# PIC32MZ.net
KiCad netlist of a schematic drawn in Altium Designer
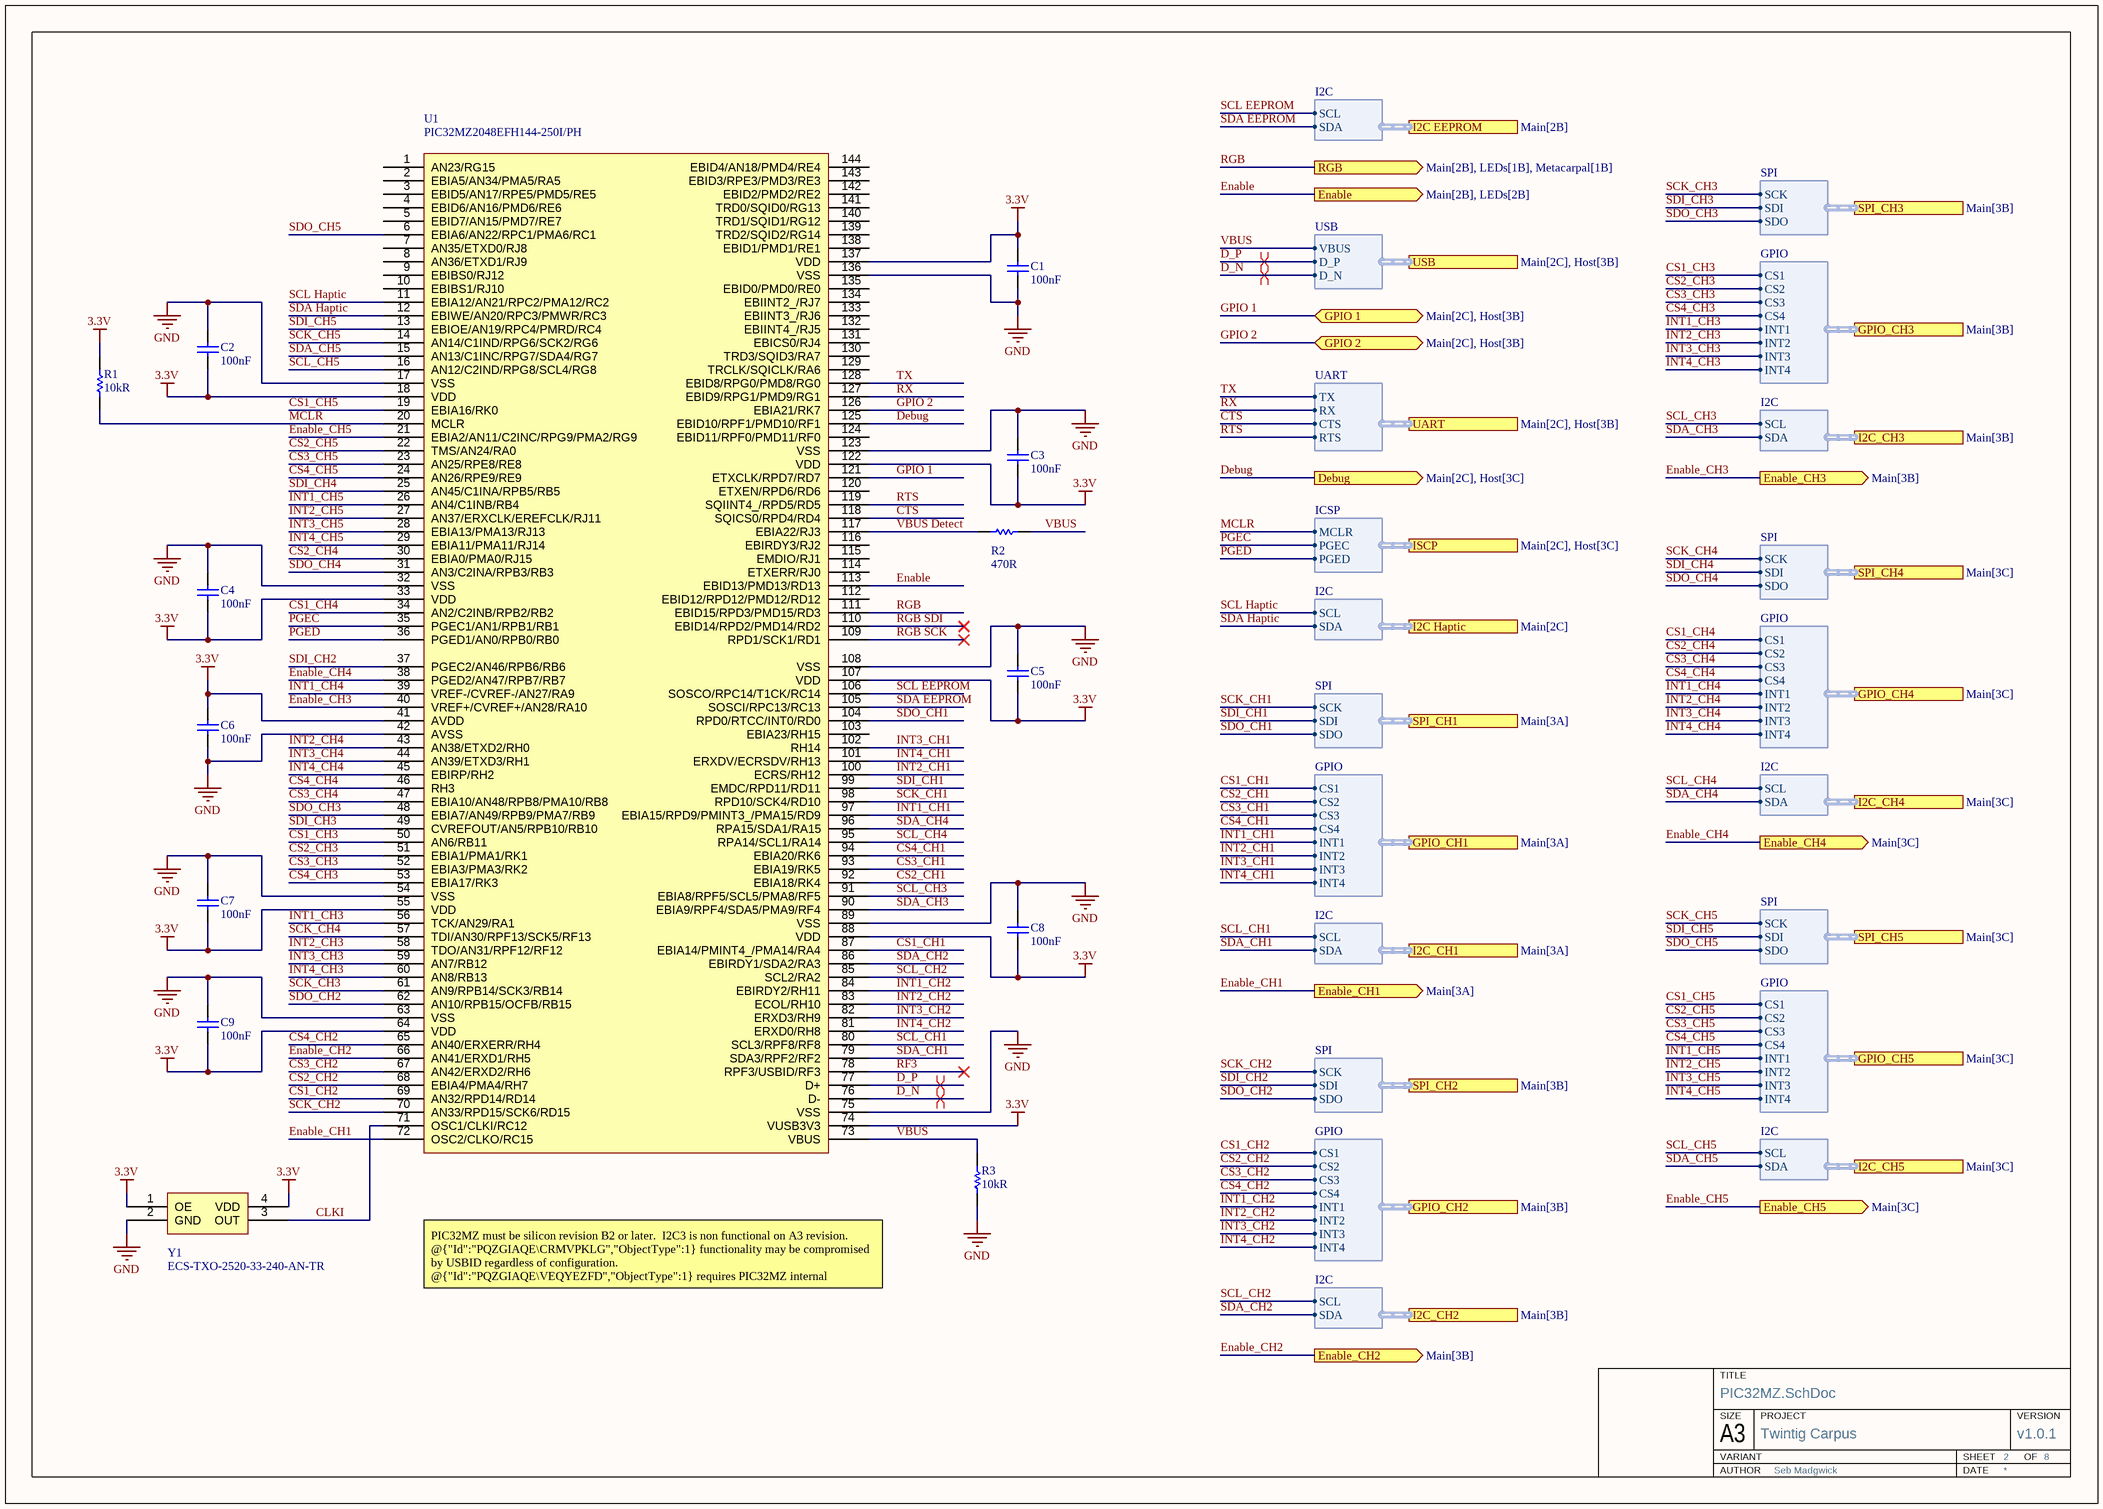
[diagram p0: PIC32MZ.SchDoc]

(export (version "E")
  (design (tool "Eeschema 10.0.6"))
  (components
    (comp (ref "C1") (value "100nF") (footprint "Capacitor 0402") (libsource (lib "x-io") (part "Capacitor")))
    (comp (ref "C2") (value "100nF") (footprint "Capacitor 0402") (libsource (lib "x-io") (part "Capacitor")))
    (comp (ref "C3") (value "100nF") (footprint "Capacitor 0402") (libsource (lib "x-io") (part "Capacitor")))
    (comp (ref "C4") (value "100nF") (footprint "Capacitor 0402") (libsource (lib "x-io") (part "Capacitor")))
    (comp (ref "C5") (value "100nF") (footprint "Capacitor 0402") (libsource (lib "x-io") (part "Capacitor")))
    (comp (ref "C6") (value "100nF") (footprint "Capacitor 0402") (libsource (lib "x-io") (part "Capacitor")))
    (comp (ref "C7") (value "100nF") (footprint "Capacitor 0402") (libsource (lib "x-io") (part "Capacitor")))
    (comp (ref "C8") (value "100nF") (footprint "Capacitor 0402") (libsource (lib "x-io") (part "Capacitor")))
    (comp (ref "C9") (value "100nF") (footprint "Capacitor 0402") (libsource (lib "x-io") (part "Capacitor")))
    (comp (ref "R1") (value "10kR") (footprint "Resistor 0402") (libsource (lib "x-io") (part "Resistor")))
    (comp (ref "R2") (value "470R") (footprint "Resistor 0402") (libsource (lib "x-io") (part "Resistor")))
    (comp (ref "R3") (value "10kR") (footprint "Resistor 0402") (libsource (lib "x-io") (part "Resistor")))
    (comp (ref "U1")
      (value "PIC32MZ2048EFH144-250I/PH")
      (footprint "TQFP-144 0.4mm")
      (libsource (lib "x-io") (part "PIC32MZ2048EFH144-250I/PH"))
    )
    (comp (ref "Y1")
      (value "ECS-TXO-2520-33-240-AN-TR")
      (footprint "ECS 2x2.5mm")
      (libsource (lib "x-io") (part "Oscillator"))
    )
  )
  (nets
    (net (code "7") (name "/CLKI") (class "Default")
      (node (ref "U1") (pin "71") (pinfunction "OSC1/CLKI/RC12_71") (pintype "passive"))
      (node (ref "Y1") (pin "3") (pinfunction "OUT_3") (pintype "passive"))
    )
    (net (code "8") (name "/CS1_CH1") (class "Default")
      (node (ref "U1") (pin "87") (pinfunction "EBIA14/PMINT4_/PMA14/RA4_87") (pintype "passive"))
    )
    (net (code "9") (name "/CS1_CH2") (class "Default")
      (node (ref "U1") (pin "69") (pinfunction "AN32/RPD14/RD14_69") (pintype "passive"))
    )
    (net (code "10") (name "/CS1_CH3") (class "Default")
      (node (ref "U1") (pin "50") (pinfunction "AN6/RB11_50") (pintype "passive"))
    )
    (net (code "11") (name "/CS1_CH4") (class "Default")
      (node (ref "U1") (pin "34") (pinfunction "AN2/C2INB/RPB2/RB2_34") (pintype "passive"))
    )
    (net (code "12") (name "/CS1_CH5") (class "Default")
      (node (ref "U1") (pin "19") (pinfunction "EBIA16/RK0_19") (pintype "passive"))
    )
    (net (code "13") (name "/CS2_CH1") (class "Default")
      (node (ref "U1") (pin "92") (pinfunction "EBIA18/RK4_92") (pintype "passive"))
    )
    (net (code "14") (name "/CS2_CH2") (class "Default")
      (node (ref "U1") (pin "68") (pinfunction "EBIA4/PMA4/RH7_68") (pintype "passive"))
    )
    (net (code "15") (name "/CS2_CH3") (class "Default")
      (node (ref "U1") (pin "51") (pinfunction "EBIA1/PMA1/RK1_51") (pintype "passive"))
    )
    (net (code "16") (name "/CS2_CH4") (class "Default")
      (node (ref "U1") (pin "30") (pinfunction "EBIA0/PMA0/RJ15_30") (pintype "passive"))
    )
    (net (code "17") (name "/CS2_CH5") (class "Default")
      (node (ref "U1") (pin "22") (pinfunction "TMS/AN24/RA0_22") (pintype "passive"))
    )
    (net (code "18") (name "/CS3_CH1") (class "Default")
      (node (ref "U1") (pin "93") (pinfunction "EBIA19/RK5_93") (pintype "passive"))
    )
    (net (code "19") (name "/CS3_CH2") (class "Default")
      (node (ref "U1") (pin "67") (pinfunction "AN42/ERXD2/RH6_67") (pintype "passive"))
    )
    (net (code "20") (name "/CS3_CH3") (class "Default")
      (node (ref "U1") (pin "52") (pinfunction "EBIA3/PMA3/RK2_52") (pintype "passive"))
    )
    (net (code "21") (name "/CS3_CH4") (class "Default")
      (node (ref "U1") (pin "47") (pinfunction "EBIA10/AN48/RPB8/PMA10/RB8_47") (pintype "passive"))
    )
    (net (code "22") (name "/CS3_CH5") (class "Default")
      (node (ref "U1") (pin "23") (pinfunction "AN25/RPE8/RE8_23") (pintype "passive"))
    )
    (net (code "23") (name "/CS4_CH1") (class "Default")
      (node (ref "U1") (pin "94") (pinfunction "EBIA20/RK6_94") (pintype "passive"))
    )
    (net (code "24") (name "/CS4_CH2") (class "Default")
      (node (ref "U1") (pin "65") (pinfunction "AN40/ERXERR/RH4_65") (pintype "passive"))
    )
    (net (code "25") (name "/CS4_CH3") (class "Default")
      (node (ref "U1") (pin "53") (pinfunction "EBIA17/RK3_53") (pintype "passive"))
    )
    (net (code "26") (name "/CS4_CH4") (class "Default")
      (node (ref "U1") (pin "46") (pinfunction "RH3_46") (pintype "passive"))
    )
    (net (code "27") (name "/CS4_CH5") (class "Default")
      (node (ref "U1") (pin "24") (pinfunction "AN26/RPE9/RE9_24") (pintype "passive"))
    )
    (net (code "28") (name "/CTS") (class "Default")
      (node (ref "U1") (pin "118") (pinfunction "SQICS0/RPD4/RD4_118") (pintype "passive"))
    )
    (net (code "29") (name "/D_N") (class "Default")
      (node (ref "U1") (pin "76") (pinfunction "D-_76") (pintype "passive"))
    )
    (net (code "30") (name "/D_P") (class "Default")
      (node (ref "U1") (pin "77") (pinfunction "D+_77") (pintype "passive"))
    )
    (net (code "31") (name "/Debug") (class "Default")
      (node (ref "U1") (pin "125") (pinfunction "EBID10/RPF1/PMD10/RF1_125") (pintype "passive"))
    )
    (net (code "32") (name "/Enable") (class "Default")
      (node (ref "U1") (pin "113") (pinfunction "EBID13/PMD13/RD13_113") (pintype "passive"))
    )
    (net (code "33") (name "/Enable_CH1") (class "Default")
      (node (ref "U1") (pin "72") (pinfunction "OSC2/CLKO/RC15_72") (pintype "passive"))
    )
    (net (code "34") (name "/Enable_CH2") (class "Default")
      (node (ref "U1") (pin "66") (pinfunction "AN41/ERXD1/RH5_66") (pintype "passive"))
    )
    (net (code "35") (name "/Enable_CH3") (class "Default")
      (node (ref "U1") (pin "40") (pinfunction "VREF+/CVREF+/AN28/RA10_40") (pintype "passive"))
    )
    (net (code "36") (name "/Enable_CH4") (class "Default")
      (node (ref "U1") (pin "38") (pinfunction "PGED2/AN47/RPB7/RB7_38") (pintype "passive"))
    )
    (net (code "37") (name "/Enable_CH5") (class "Default")
      (node (ref "U1") (pin "21") (pinfunction "EBIA2/AN11/C2INC/RPG9/PMA2/RG9_21") (pintype "passive"))
    )
    (net (code "38") (name "/GPIO 1") (class "Default")
      (node (ref "U1") (pin "121") (pinfunction "ETXCLK/RPD7/RD7_121") (pintype "passive"))
    )
    (net (code "39") (name "/GPIO 2") (class "Default")
      (node (ref "U1") (pin "126") (pinfunction "EBIA21/RK7_126") (pintype "passive"))
    )
    (net (code "40") (name "/INT1_CH1") (class "Default")
      (node (ref "U1") (pin "97") (pinfunction "EBIA15/RPD9/PMINT3_/PMA15/RD9_97") (pintype "passive"))
    )
    (net (code "41") (name "/INT1_CH2") (class "Default")
      (node (ref "U1") (pin "84") (pinfunction "EBIRDY2/RH11_84") (pintype "passive"))
    )
    (net (code "42") (name "/INT1_CH3") (class "Default")
      (node (ref "U1") (pin "56") (pinfunction "TCK/AN29/RA1_56") (pintype "passive"))
    )
    (net (code "43") (name "/INT1_CH4") (class "Default")
      (node (ref "U1") (pin "39") (pinfunction "VREF-/CVREF-/AN27/RA9_39") (pintype "passive"))
    )
    (net (code "44") (name "/INT1_CH5") (class "Default")
      (node (ref "U1") (pin "26") (pinfunction "AN4/C1INB/RB4_26") (pintype "passive"))
    )
    (net (code "45") (name "/INT2_CH1") (class "Default")
      (node (ref "U1") (pin "100") (pinfunction "ECRS/RH12_100") (pintype "passive"))
    )
    (net (code "46") (name "/INT2_CH2") (class "Default")
      (node (ref "U1") (pin "83") (pinfunction "ECOL/RH10_83") (pintype "passive"))
    )
    (net (code "47") (name "/INT2_CH3") (class "Default")
      (node (ref "U1") (pin "58") (pinfunction "TDO/AN31/RPF12/RF12_58") (pintype "passive"))
    )
    (net (code "48") (name "/INT2_CH4") (class "Default")
      (node (ref "U1") (pin "43") (pinfunction "AN38/ETXD2/RH0_43") (pintype "passive"))
    )
    (net (code "49") (name "/INT2_CH5") (class "Default")
      (node (ref "U1") (pin "27") (pinfunction "AN37/ERXCLK/EREFCLK/RJ11_27") (pintype "passive"))
    )
    (net (code "50") (name "/INT3_CH1") (class "Default")
      (node (ref "U1") (pin "102") (pinfunction "RH14_102") (pintype "passive"))
    )
    (net (code "51") (name "/INT3_CH2") (class "Default")
      (node (ref "U1") (pin "82") (pinfunction "ERXD3/RH9_82") (pintype "passive"))
    )
    (net (code "52") (name "/INT3_CH3") (class "Default")
      (node (ref "U1") (pin "59") (pinfunction "AN7/RB12_59") (pintype "passive"))
    )
    (net (code "53") (name "/INT3_CH4") (class "Default")
      (node (ref "U1") (pin "44") (pinfunction "AN39/ETXD3/RH1_44") (pintype "passive"))
    )
    (net (code "54") (name "/INT3_CH5") (class "Default")
      (node (ref "U1") (pin "28") (pinfunction "EBIA13/PMA13/RJ13_28") (pintype "passive"))
    )
    (net (code "55") (name "/INT4_CH1") (class "Default")
      (node (ref "U1") (pin "101") (pinfunction "ERXDV/ECRSDV/RH13_101") (pintype "passive"))
    )
    (net (code "56") (name "/INT4_CH2") (class "Default")
      (node (ref "U1") (pin "81") (pinfunction "ERXD0/RH8_81") (pintype "passive"))
    )
    (net (code "57") (name "/INT4_CH3") (class "Default")
      (node (ref "U1") (pin "60") (pinfunction "AN8/RB13_60") (pintype "passive"))
    )
    (net (code "58") (name "/INT4_CH4") (class "Default")
      (node (ref "U1") (pin "45") (pinfunction "EBIRP/RH2_45") (pintype "passive"))
    )
    (net (code "59") (name "/INT4_CH5") (class "Default")
      (node (ref "U1") (pin "29") (pinfunction "EBIA11/PMA11/RJ14_29") (pintype "passive"))
    )
    (net (code "60") (name "/MCLR") (class "Default")
      (node (ref "R1") (pin "1") (pinfunction "1_1") (pintype "passive"))
      (node (ref "U1") (pin "20") (pinfunction "MCLR_20") (pintype "passive"))
    )
    (net (code "61") (name "/PGEC") (class "Default")
      (node (ref "U1") (pin "35") (pinfunction "PGEC1/AN1/RPB1/RB1_35") (pintype "passive"))
    )
    (net (code "62") (name "/PGED") (class "Default")
      (node (ref "U1") (pin "36") (pinfunction "PGED1/AN0/RPB0/RB0_36") (pintype "passive"))
    )
    (net (code "63") (name "/RF3") (class "Default")
      (node (ref "U1") (pin "78") (pinfunction "RPF3/USBID/RF3_78") (pintype "passive+no_connect"))
    )
    (net (code "64") (name "/RGB") (class "Default")
      (node (ref "U1") (pin "111") (pinfunction "EBID15/RPD3/PMD15/RD3_111") (pintype "passive"))
    )
    (net (code "65") (name "/RGB SCK") (class "Default")
      (node (ref "U1") (pin "109") (pinfunction "RPD1/SCK1/RD1_109") (pintype "passive+no_connect"))
    )
    (net (code "66") (name "/RGB SDI") (class "Default")
      (node (ref "U1") (pin "110") (pinfunction "EBID14/RPD2/PMD14/RD2_110") (pintype "passive+no_connect"))
    )
    (net (code "67") (name "/RTS") (class "Default")
      (node (ref "U1") (pin "119") (pinfunction "SQIINT4_/RPD5/RD5_119") (pintype "passive"))
    )
    (net (code "68") (name "/RX") (class "Default")
      (node (ref "U1") (pin "127") (pinfunction "EBID9/RPG1/PMD9/RG1_127") (pintype "passive"))
    )
    (net (code "69") (name "/SCK_CH1") (class "Default")
      (node (ref "U1") (pin "98") (pinfunction "RPD10/SCK4/RD10_98") (pintype "passive"))
    )
    (net (code "70") (name "/SCK_CH2") (class "Default")
      (node (ref "U1") (pin "70") (pinfunction "AN33/RPD15/SCK6/RD15_70") (pintype "passive"))
    )
    (net (code "71") (name "/SCK_CH3") (class "Default")
      (node (ref "U1") (pin "61") (pinfunction "AN9/RPB14/SCK3/RB14_61") (pintype "passive"))
    )
    (net (code "72") (name "/SCK_CH4") (class "Default")
      (node (ref "U1") (pin "57") (pinfunction "TDI/AN30/RPF13/SCK5/RF13_57") (pintype "passive"))
    )
    (net (code "73") (name "/SCK_CH5") (class "Default")
      (node (ref "U1") (pin "14") (pinfunction "AN14/C1IND/RPG6/SCK2/RG6_14") (pintype "passive"))
    )
    (net (code "74") (name "/SCL EEPROM") (class "Default")
      (node (ref "U1") (pin "106") (pinfunction "SOSCO/RPC14/T1CK/RC14_106") (pintype "passive"))
    )
    (net (code "75") (name "/SCL Haptic") (class "Default")
      (node (ref "U1") (pin "11") (pinfunction "EBIA12/AN21/RPC2/PMA12/RC2_11") (pintype "passive"))
    )
    (net (code "76") (name "/SCL_CH1") (class "Default")
      (node (ref "U1") (pin "80") (pinfunction "SCL3/RPF8/RF8_80") (pintype "passive"))
    )
    (net (code "77") (name "/SCL_CH2") (class "Default")
      (node (ref "U1") (pin "85") (pinfunction "SCL2/RA2_85") (pintype "passive"))
    )
    (net (code "78") (name "/SCL_CH3") (class "Default")
      (node (ref "U1") (pin "91") (pinfunction "EBIA8/RPF5/SCL5/PMA8/RF5_91") (pintype "passive"))
    )
    (net (code "79") (name "/SCL_CH4") (class "Default")
      (node (ref "U1") (pin "95") (pinfunction "RPA14/SCL1/RA14_95") (pintype "passive"))
    )
    (net (code "80") (name "/SCL_CH5") (class "Default")
      (node (ref "U1") (pin "16") (pinfunction "AN12/C2IND/RPG8/SCL4/RG8_16") (pintype "passive"))
    )
    (net (code "81") (name "/SDA EEPROM") (class "Default")
      (node (ref "U1") (pin "105") (pinfunction "SOSCI/RPC13/RC13_105") (pintype "passive"))
    )
    (net (code "82") (name "/SDA Haptic") (class "Default")
      (node (ref "U1") (pin "12") (pinfunction "EBIWE/AN20/RPC3/PMWR/RC3_12") (pintype "passive"))
    )
    (net (code "83") (name "/SDA_CH1") (class "Default")
      (node (ref "U1") (pin "79") (pinfunction "SDA3/RPF2/RF2_79") (pintype "passive"))
    )
    (net (code "84") (name "/SDA_CH2") (class "Default")
      (node (ref "U1") (pin "86") (pinfunction "EBIRDY1/SDA2/RA3_86") (pintype "passive"))
    )
    (net (code "85") (name "/SDA_CH3") (class "Default")
      (node (ref "U1") (pin "90") (pinfunction "EBIA9/RPF4/SDA5/PMA9/RF4_90") (pintype "passive"))
    )
    (net (code "86") (name "/SDA_CH4") (class "Default")
      (node (ref "U1") (pin "96") (pinfunction "RPA15/SDA1/RA15_96") (pintype "passive"))
    )
    (net (code "87") (name "/SDA_CH5") (class "Default")
      (node (ref "U1") (pin "15") (pinfunction "AN13/C1INC/RPG7/SDA4/RG7_15") (pintype "passive"))
    )
    (net (code "88") (name "/SDI_CH1") (class "Default")
      (node (ref "U1") (pin "99") (pinfunction "EMDC/RPD11/RD11_99") (pintype "passive"))
    )
    (net (code "89") (name "/SDI_CH2") (class "Default")
      (node (ref "U1") (pin "37") (pinfunction "PGEC2/AN46/RPB6/RB6_37") (pintype "passive"))
    )
    (net (code "90") (name "/SDI_CH3") (class "Default")
      (node (ref "U1") (pin "49") (pinfunction "CVREFOUT/AN5/RPB10/RB10_49") (pintype "passive"))
    )
    (net (code "91") (name "/SDI_CH4") (class "Default")
      (node (ref "U1") (pin "25") (pinfunction "AN45/C1INA/RPB5/RB5_25") (pintype "passive"))
    )
    (net (code "92") (name "/SDI_CH5") (class "Default")
      (node (ref "U1") (pin "13") (pinfunction "EBIOE/AN19/RPC4/PMRD/RC4_13") (pintype "passive"))
    )
    (net (code "93") (name "/SDO_CH1") (class "Default")
      (node (ref "U1") (pin "104") (pinfunction "RPD0/RTCC/INT0/RD0_104") (pintype "passive"))
    )
    (net (code "94") (name "/SDO_CH2") (class "Default")
      (node (ref "U1") (pin "62") (pinfunction "AN10/RPB15/OCFB/RB15_62") (pintype "passive"))
    )
    (net (code "95") (name "/SDO_CH3") (class "Default")
      (node (ref "U1") (pin "48") (pinfunction "EBIA7/AN49/RPB9/PMA7/RB9_48") (pintype "passive"))
    )
    (net (code "96") (name "/SDO_CH4") (class "Default")
      (node (ref "U1") (pin "31") (pinfunction "AN3/C2INA/RPB3/RB3_31") (pintype "passive"))
    )
    (net (code "97") (name "/SDO_CH5") (class "Default")
      (node (ref "U1") (pin "6") (pinfunction "EBIA6/AN22/RPC1/PMA6/RC1_6") (pintype "passive"))
    )
    (net (code "98") (name "/TX") (class "Default")
      (node (ref "U1") (pin "128") (pinfunction "EBID8/RPG0/PMD8/RG0_128") (pintype "passive"))
    )
    (net (code "99") (name "/VBUS") (class "Default")
      (node (ref "R2") (pin "1") (pinfunction "1_1") (pintype "passive"))
      (node (ref "R3") (pin "2") (pinfunction "2_2") (pintype "passive"))
      (node (ref "U1") (pin "73") (pinfunction "VBUS_73") (pintype "passive"))
    )
    (net (code "100") (name "/VBUS Detect") (class "Default")
      (node (ref "R2") (pin "2") (pinfunction "2_2") (pintype "passive"))
      (node (ref "U1") (pin "117") (pinfunction "EBIA22/RJ3_117") (pintype "passive"))
    )
    (net (code "107") (name "3.3V") (class "Default")
      (node (ref "C1") (pin "2") (pinfunction "2_2") (pintype "passive"))
      (node (ref "C2") (pin "1") (pinfunction "1_1") (pintype "passive"))
      (node (ref "C3") (pin "1") (pinfunction "1_1") (pintype "passive"))
      (node (ref "C4") (pin "1") (pinfunction "1_1") (pintype "passive"))
      (node (ref "C5") (pin "1") (pinfunction "1_1") (pintype "passive"))
      (node (ref "C6") (pin "2") (pinfunction "2_2") (pintype "passive"))
      (node (ref "C7") (pin "1") (pinfunction "1_1") (pintype "passive"))
      (node (ref "C8") (pin "1") (pinfunction "1_1") (pintype "passive"))
      (node (ref "C9") (pin "1") (pinfunction "1_1") (pintype "passive"))
      (node (ref "R1") (pin "2") (pinfunction "2_2") (pintype "passive"))
      (node (ref "U1") (pin "107") (pinfunction "VDD_107") (pintype "passive"))
      (node (ref "U1") (pin "122") (pinfunction "VDD_122") (pintype "passive"))
      (node (ref "U1") (pin "137") (pinfunction "VDD_137") (pintype "passive"))
      (node (ref "U1") (pin "18") (pinfunction "VDD_18") (pintype "passive"))
      (node (ref "U1") (pin "33") (pinfunction "VDD_33") (pintype "passive"))
      (node (ref "U1") (pin "41") (pinfunction "AVDD_41") (pintype "passive"))
      (node (ref "U1") (pin "55") (pinfunction "VDD_55") (pintype "passive"))
      (node (ref "U1") (pin "64") (pinfunction "VDD_64") (pintype "passive"))
      (node (ref "U1") (pin "74") (pinfunction "VUSB3V3_74") (pintype "passive"))
      (node (ref "U1") (pin "88") (pinfunction "VDD_88") (pintype "passive"))
      (node (ref "Y1") (pin "1") (pinfunction "OE_1") (pintype "passive"))
      (node (ref "Y1") (pin "4") (pinfunction "VDD_4") (pintype "passive"))
    )
    (net (code "108") (name "GND") (class "Default")
      (node (ref "C1") (pin "1") (pinfunction "1_1") (pintype "passive"))
      (node (ref "C2") (pin "2") (pinfunction "2_2") (pintype "passive"))
      (node (ref "C3") (pin "2") (pinfunction "2_2") (pintype "passive"))
      (node (ref "C4") (pin "2") (pinfunction "2_2") (pintype "passive"))
      (node (ref "C5") (pin "2") (pinfunction "2_2") (pintype "passive"))
      (node (ref "C6") (pin "1") (pinfunction "1_1") (pintype "passive"))
      (node (ref "C7") (pin "2") (pinfunction "2_2") (pintype "passive"))
      (node (ref "C8") (pin "2") (pinfunction "2_2") (pintype "passive"))
      (node (ref "C9") (pin "2") (pinfunction "2_2") (pintype "passive"))
      (node (ref "R3") (pin "1") (pinfunction "1_1") (pintype "passive"))
      (node (ref "U1") (pin "108") (pinfunction "VSS_108") (pintype "passive"))
      (node (ref "U1") (pin "123") (pinfunction "VSS_123") (pintype "passive"))
      (node (ref "U1") (pin "136") (pinfunction "VSS_136") (pintype "passive"))
      (node (ref "U1") (pin "17") (pinfunction "VSS_17") (pintype "passive"))
      (node (ref "U1") (pin "32") (pinfunction "VSS_32") (pintype "passive"))
      (node (ref "U1") (pin "42") (pinfunction "AVSS_42") (pintype "passive"))
      (node (ref "U1") (pin "54") (pinfunction "VSS_54") (pintype "passive"))
      (node (ref "U1") (pin "63") (pinfunction "VSS_63") (pintype "passive"))
      (node (ref "U1") (pin "75") (pinfunction "VSS_75") (pintype "passive"))
      (node (ref "U1") (pin "89") (pinfunction "VSS_89") (pintype "passive"))
      (node (ref "Y1") (pin "2") (pinfunction "GND_2") (pintype "passive"))
    )
    (net (code "109") (name "unconnected-(U1-AN23{slash}RG15-Pad1)") (class "Default")
      (node (ref "U1") (pin "1") (pinfunction "AN23/RG15_1") (pintype "passive"))
    )
    (net (code "110") (name "unconnected-(U1-AN35{slash}ETXD0{slash}RJ8-Pad7)") (class "Default")
      (node (ref "U1") (pin "7") (pinfunction "AN35/ETXD0/RJ8_7") (pintype "passive"))
    )
    (net (code "111") (name "unconnected-(U1-AN36{slash}ETXD1{slash}RJ9-Pad8)") (class "Default")
      (node (ref "U1") (pin "8") (pinfunction "AN36/ETXD1/RJ9_8") (pintype "passive"))
    )
    (net (code "112") (name "unconnected-(U1-EBIA5{slash}AN34{slash}PMA5{slash}RA5-Pad2)") (class "Default")
      (node (ref "U1") (pin "2") (pinfunction "EBIA5/AN34/PMA5/RA5_2") (pintype "passive"))
    )
    (net (code "113") (name "unconnected-(U1-EBIA23{slash}RH15-Pad103)") (class "Default")
      (node (ref "U1") (pin "103") (pinfunction "EBIA23/RH15_103") (pintype "passive"))
    )
    (net (code "114") (name "unconnected-(U1-EBIBS0{slash}RJ12-Pad9)") (class "Default")
      (node (ref "U1") (pin "9") (pinfunction "EBIBS0/RJ12_9") (pintype "passive"))
    )
    (net (code "115") (name "unconnected-(U1-EBIBS1{slash}RJ10-Pad10)") (class "Default")
      (node (ref "U1") (pin "10") (pinfunction "EBIBS1/RJ10_10") (pintype "passive"))
    )
    (net (code "116") (name "unconnected-(U1-EBICS0{slash}RJ4-Pad131)") (class "Default")
      (node (ref "U1") (pin "131") (pinfunction "EBICS0/RJ4_131") (pintype "passive"))
    )
    (net (code "117") (name "unconnected-(U1-EBID0{slash}PMD0{slash}RE0-Pad135)") (class "Default")
      (node (ref "U1") (pin "135") (pinfunction "EBID0/PMD0/RE0_135") (pintype "passive"))
    )
    (net (code "118") (name "unconnected-(U1-EBID1{slash}PMD1{slash}RE1-Pad138)") (class "Default")
      (node (ref "U1") (pin "138") (pinfunction "EBID1/PMD1/RE1_138") (pintype "passive"))
    )
    (net (code "119") (name "unconnected-(U1-EBID2{slash}PMD2{slash}RE2-Pad142)") (class "Default")
      (node (ref "U1") (pin "142") (pinfunction "EBID2/PMD2/RE2_142") (pintype "passive"))
    )
    (net (code "120") (name "unconnected-(U1-EBID3{slash}RPE3{slash}PMD3{slash}RE3-Pad143)") (class "Default")
      (node (ref "U1") (pin "143") (pinfunction "EBID3/RPE3/PMD3/RE3_143") (pintype "passive"))
    )
    (net (code "121") (name "unconnected-(U1-EBID4{slash}AN18{slash}PMD4{slash}RE4-Pad144)") (class "Default")
      (node (ref "U1") (pin "144") (pinfunction "EBID4/AN18/PMD4/RE4_144") (pintype "passive"))
    )
    (net (code "122") (name "unconnected-(U1-EBID5{slash}AN17{slash}RPE5{slash}PMD5{slash}RE5-Pad3)") (class "Default")
      (node (ref "U1") (pin "3") (pinfunction "EBID5/AN17/RPE5/PMD5/RE5_3") (pintype "passive"))
    )
    (net (code "123") (name "unconnected-(U1-EBID6{slash}AN16{slash}PMD6{slash}RE6-Pad4)") (class "Default")
      (node (ref "U1") (pin "4") (pinfunction "EBID6/AN16/PMD6/RE6_4") (pintype "passive"))
    )
    (net (code "124") (name "unconnected-(U1-EBID7{slash}AN15{slash}PMD7{slash}RE7-Pad5)") (class "Default")
      (node (ref "U1") (pin "5") (pinfunction "EBID7/AN15/PMD7/RE7_5") (pintype "passive"))
    )
    (net (code "125") (name "unconnected-(U1-EBID11{slash}RPF0{slash}PMD11{slash}RF0-Pad124)") (class "Default")
      (node (ref "U1") (pin "124") (pinfunction "EBID11/RPF0/PMD11/RF0_124") (pintype "passive"))
    )
    (net (code "126") (name "unconnected-(U1-EBID12{slash}RPD12{slash}PMD12{slash}RD12-Pad112)") (class "Default")
      (node (ref "U1") (pin "112") (pinfunction "EBID12/RPD12/PMD12/RD12_112") (pintype "passive"))
    )
    (net (code "127") (name "unconnected-(U1-EBIINT2_{slash}RJ7-Pad134)") (class "Default")
      (node (ref "U1") (pin "134") (pinfunction "EBIINT2_/RJ7_134") (pintype "passive"))
    )
    (net (code "128") (name "unconnected-(U1-EBIINT3_{slash}RJ6-Pad133)") (class "Default")
      (node (ref "U1") (pin "133") (pinfunction "EBIINT3_/RJ6_133") (pintype "passive"))
    )
    (net (code "129") (name "unconnected-(U1-EBIINT4_{slash}RJ5-Pad132)") (class "Default")
      (node (ref "U1") (pin "132") (pinfunction "EBIINT4_/RJ5_132") (pintype "passive"))
    )
    (net (code "130") (name "unconnected-(U1-EBIRDY3{slash}RJ2-Pad116)") (class "Default")
      (node (ref "U1") (pin "116") (pinfunction "EBIRDY3/RJ2_116") (pintype "passive"))
    )
    (net (code "131") (name "unconnected-(U1-EMDIO{slash}RJ1-Pad115)") (class "Default")
      (node (ref "U1") (pin "115") (pinfunction "EMDIO/RJ1_115") (pintype "passive"))
    )
    (net (code "132") (name "unconnected-(U1-ETXEN{slash}RPD6{slash}RD6-Pad120)") (class "Default")
      (node (ref "U1") (pin "120") (pinfunction "ETXEN/RPD6/RD6_120") (pintype "passive"))
    )
    (net (code "133") (name "unconnected-(U1-ETXERR{slash}RJ0-Pad114)") (class "Default")
      (node (ref "U1") (pin "114") (pinfunction "ETXERR/RJ0_114") (pintype "passive"))
    )
    (net (code "134") (name "unconnected-(U1-TRCLK{slash}SQICLK{slash}RA6-Pad129)") (class "Default")
      (node (ref "U1") (pin "129") (pinfunction "TRCLK/SQICLK/RA6_129") (pintype "passive"))
    )
    (net (code "135") (name "unconnected-(U1-TRD0{slash}SQID0{slash}RG13-Pad141)") (class "Default")
      (node (ref "U1") (pin "141") (pinfunction "TRD0/SQID0/RG13_141") (pintype "passive"))
    )
    (net (code "136") (name "unconnected-(U1-TRD1{slash}SQID1{slash}RG12-Pad140)") (class "Default")
      (node (ref "U1") (pin "140") (pinfunction "TRD1/SQID1/RG12_140") (pintype "passive"))
    )
    (net (code "137") (name "unconnected-(U1-TRD2{slash}SQID2{slash}RG14-Pad139)") (class "Default")
      (node (ref "U1") (pin "139") (pinfunction "TRD2/SQID2/RG14_139") (pintype "passive"))
    )
    (net (code "138") (name "unconnected-(U1-TRD3{slash}SQID3{slash}RA7-Pad130)") (class "Default")
      (node (ref "U1") (pin "130") (pinfunction "TRD3/SQID3/RA7_130") (pintype "passive"))
    )
  )
)
